# untitled.net
KiCad netlist of a schematic drawn in EAGLE
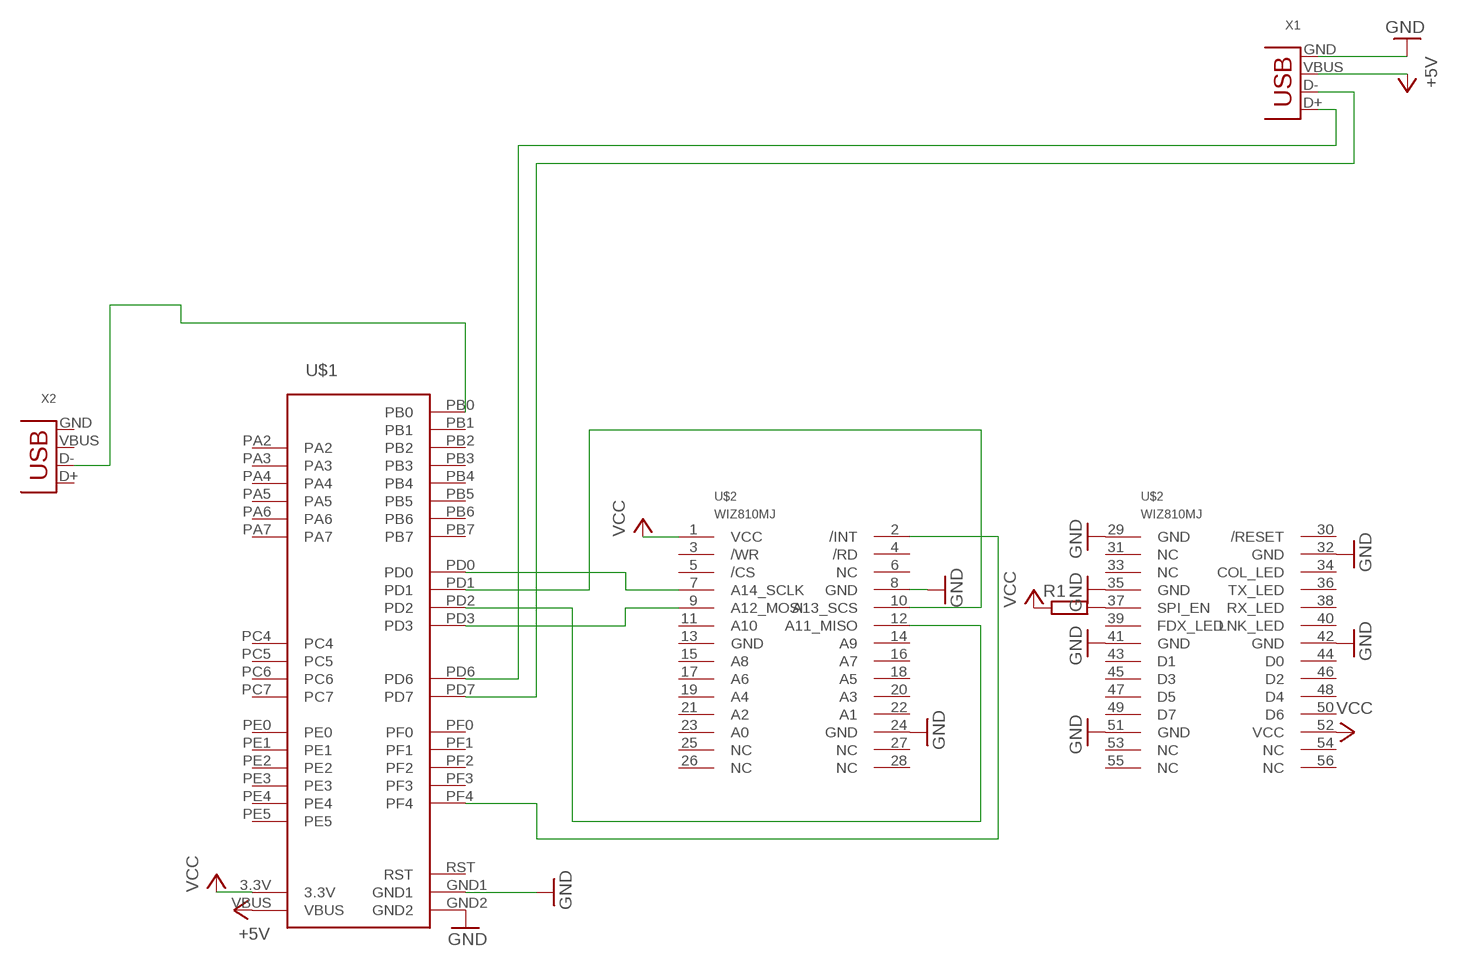
[diagram p0: schematic, sheet 1]

(export (version "E")
  (design (tool "Eeschema 10.0.6"))
  (components
    (comp (ref "R1")
      (value "R-EU_0204/5")
      (footprint "eagle-import:0204_5")
      (libsource (lib "eagle-import") (part "R-EU_0204/5"))
    )
    (comp (ref "U$1")
      (value "STELLARIS-LAUNCHPADSTELLARIS-LAUNCHPAD-XL")
      (footprint "eagle-import:LAUNCHPAD-XL")
      (libsource (lib "eagle-import") (part "STELLARIS-LAUNCHPADSTELLARIS-LAUNCHPAD-XL"))
    )
    (comp (ref "U$2")
      (value "WIZ810MJ")
      (footprint "eagle-import:WIZ810MJ")
      (libsource (lib "eagle-import") (part "WIZ810MJ"))
    )
    (comp (ref "X1")
      (value "USB-A-H")
      (footprint "eagle-import:USB-A-H")
      (libsource (lib "eagle-import") (part "USB-A-H"))
    )
    (comp (ref "X2")
      (value "USB-A-H")
      (footprint "eagle-import:USB-A-H")
      (libsource (lib "eagle-import") (part "USB-A-H"))
    )
  )
  (nets
    (net (code "1") (name "+5V") (class "Default")
      (node (ref "U$1") (pin "VBUS") (pinfunction "VBUS_VBUS") (pintype "power_in"))
      (node (ref "X1") (pin "VBUS") (pinfunction "VBUS_VBUS") (pintype "bidirectional"))
    )
    (net (code "2") (name "/RST") (class "Default")
      (node (ref "U$1") (pin "RST") (pinfunction "RST_RST") (pintype "power_in"))
    )
    (net (code "3") (name "GND") (class "Default")
      (node (ref "U$1") (pin "GND1") (pinfunction "GND1_GND1") (pintype "bidirectional"))
      (node (ref "U$1") (pin "GND2") (pinfunction "GND2_GND2") (pintype "power_in"))
      (node (ref "U$2") (pin "24") (pinfunction "GND_24") (pintype "bidirectional"))
      (node (ref "U$2") (pin "29") (pinfunction "GND_29") (pintype "bidirectional"))
      (node (ref "U$2") (pin "32") (pinfunction "GND_32") (pintype "bidirectional"))
      (node (ref "U$2") (pin "35") (pinfunction "GND_35") (pintype "bidirectional"))
      (node (ref "U$2") (pin "41") (pinfunction "GND_41") (pintype "bidirectional"))
      (node (ref "U$2") (pin "42") (pinfunction "GND_42") (pintype "bidirectional"))
      (node (ref "U$2") (pin "51") (pinfunction "GND_51") (pintype "bidirectional"))
      (node (ref "U$2") (pin "8") (pinfunction "GND_8") (pintype "bidirectional"))
      (node (ref "X1") (pin "GND") (pinfunction "GND_GND") (pintype "bidirectional"))
    )
    (net (code "4") (name "Net-(U$1-PadPB0)") (class "Default")
      (node (ref "U$1") (pin "PB0") (pinfunction "PB0_PB0") (pintype "bidirectional"))
      (node (ref "X2") (pin "D-") (pinfunction "D-_D-") (pintype "bidirectional"))
    )
    (net (code "5") (name "Net-(U$1-PadPD6)") (class "Default")
      (node (ref "U$1") (pin "PD6") (pinfunction "PD6_PD6") (pintype "bidirectional"))
      (node (ref "X1") (pin "D+") (pinfunction "D+_D+") (pintype "bidirectional"))
    )
    (net (code "6") (name "Net-(U$1-PadPD7)") (class "Default")
      (node (ref "U$1") (pin "PD7") (pinfunction "PD7_PD7") (pintype "bidirectional"))
      (node (ref "X1") (pin "D-") (pinfunction "D-_D-") (pintype "bidirectional"))
    )
    (net (code "7") (name "Net-(U$2-A11_MISO)") (class "Default")
      (node (ref "U$1") (pin "PD2") (pinfunction "PD2_PD2") (pintype "bidirectional"))
      (node (ref "U$2") (pin "12") (pinfunction "A11_MISO_12") (pintype "bidirectional"))
    )
    (net (code "8") (name "Net-(U$2-A12_MOSI)") (class "Default")
      (node (ref "U$1") (pin "PD3") (pinfunction "PD3_PD3") (pintype "bidirectional"))
      (node (ref "U$2") (pin "9") (pinfunction "A12_MOSI_9") (pintype "bidirectional"))
    )
    (net (code "9") (name "Net-(U$2-A13_SCS)") (class "Default")
      (node (ref "U$1") (pin "PD1") (pinfunction "PD1_PD1") (pintype "bidirectional"))
      (node (ref "U$2") (pin "10") (pinfunction "A13_SCS_10") (pintype "bidirectional"))
    )
    (net (code "10") (name "Net-(U$2-A14_SCLK)") (class "Default")
      (node (ref "U$1") (pin "PD0") (pinfunction "PD0_PD0") (pintype "bidirectional"))
      (node (ref "U$2") (pin "7") (pinfunction "A14_SCLK_7") (pintype "bidirectional"))
    )
    (net (code "11") (name "Net-(U$2-SPI_EN)") (class "Default")
      (node (ref "R1") (pin "2") (pinfunction "2_2") (pintype "passive"))
      (node (ref "U$2") (pin "37") (pinfunction "SPI_EN_37") (pintype "bidirectional"))
    )
    (net (code "12") (name "Net-(U$2-{slash}INT)") (class "Default")
      (node (ref "U$1") (pin "PF4") (pinfunction "PF4_PF4") (pintype "bidirectional"))
      (node (ref "U$2") (pin "2") (pinfunction "/INT_2") (pintype "bidirectional"))
    )
    (net (code "13") (name "VCC") (class "Default")
      (node (ref "R1") (pin "1") (pinfunction "1_1") (pintype "passive"))
      (node (ref "U$1") (pin "3.3V") (pinfunction "3.3V_3.3V") (pintype "power_in"))
      (node (ref "U$2") (pin "1") (pinfunction "VCC_1") (pintype "bidirectional"))
      (node (ref "U$2") (pin "52") (pinfunction "VCC_52") (pintype "bidirectional"))
    )
    (net (code "14") (name "unconnected-(U$1-PadPA2)") (class "Default")
      (node (ref "U$1") (pin "PA2") (pinfunction "PA2_PA2") (pintype "bidirectional"))
    )
    (net (code "15") (name "unconnected-(U$1-PadPA3)") (class "Default")
      (node (ref "U$1") (pin "PA3") (pinfunction "PA3_PA3") (pintype "bidirectional"))
    )
    (net (code "16") (name "unconnected-(U$1-PadPA4)") (class "Default")
      (node (ref "U$1") (pin "PA4") (pinfunction "PA4_PA4") (pintype "bidirectional"))
    )
    (net (code "17") (name "unconnected-(U$1-PadPA5)") (class "Default")
      (node (ref "U$1") (pin "PA5") (pinfunction "PA5_PA5") (pintype "bidirectional"))
    )
    (net (code "18") (name "unconnected-(U$1-PadPA6)") (class "Default")
      (node (ref "U$1") (pin "PA6") (pinfunction "PA6_PA6") (pintype "bidirectional"))
    )
    (net (code "19") (name "unconnected-(U$1-PadPA7)") (class "Default")
      (node (ref "U$1") (pin "PA7") (pinfunction "PA7_PA7") (pintype "bidirectional"))
    )
    (net (code "20") (name "unconnected-(U$1-PadPB1)") (class "Default")
      (node (ref "U$1") (pin "PB1") (pinfunction "PB1_PB1") (pintype "bidirectional"))
    )
    (net (code "21") (name "unconnected-(U$1-PadPB2)") (class "Default")
      (node (ref "U$1") (pin "PB2") (pinfunction "PB2_PB2") (pintype "bidirectional"))
    )
    (net (code "22") (name "unconnected-(U$1-PadPB3)") (class "Default")
      (node (ref "U$1") (pin "PB3") (pinfunction "PB3_PB3") (pintype "bidirectional"))
    )
    (net (code "23") (name "unconnected-(U$1-PadPB4)") (class "Default")
      (node (ref "U$1") (pin "PB4") (pinfunction "PB4_PB4") (pintype "bidirectional"))
    )
    (net (code "24") (name "unconnected-(U$1-PadPB5)") (class "Default")
      (node (ref "U$1") (pin "PB5") (pinfunction "PB5_PB5") (pintype "bidirectional"))
    )
    (net (code "25") (name "unconnected-(U$1-PadPB6)") (class "Default")
      (node (ref "U$1") (pin "PB6") (pinfunction "PB6_PB6") (pintype "bidirectional"))
    )
    (net (code "26") (name "unconnected-(U$1-PadPB7)") (class "Default")
      (node (ref "U$1") (pin "PB7") (pinfunction "PB7_PB7") (pintype "bidirectional"))
    )
    (net (code "27") (name "unconnected-(U$1-PadPC4)") (class "Default")
      (node (ref "U$1") (pin "PC4") (pinfunction "PC4_PC4") (pintype "bidirectional"))
    )
    (net (code "28") (name "unconnected-(U$1-PadPC5)") (class "Default")
      (node (ref "U$1") (pin "PC5") (pinfunction "PC5_PC5") (pintype "bidirectional"))
    )
    (net (code "29") (name "unconnected-(U$1-PadPC6)") (class "Default")
      (node (ref "U$1") (pin "PC6") (pinfunction "PC6_PC6") (pintype "bidirectional"))
    )
    (net (code "30") (name "unconnected-(U$1-PadPC7)") (class "Default")
      (node (ref "U$1") (pin "PC7") (pinfunction "PC7_PC7") (pintype "bidirectional"))
    )
    (net (code "31") (name "unconnected-(U$1-PadPE0)") (class "Default")
      (node (ref "U$1") (pin "PE0") (pinfunction "PE0_PE0") (pintype "bidirectional"))
    )
    (net (code "32") (name "unconnected-(U$1-PadPE1)") (class "Default")
      (node (ref "U$1") (pin "PE1") (pinfunction "PE1_PE1") (pintype "bidirectional"))
    )
    (net (code "33") (name "unconnected-(U$1-PadPE2)") (class "Default")
      (node (ref "U$1") (pin "PE2") (pinfunction "PE2_PE2") (pintype "bidirectional"))
    )
    (net (code "34") (name "unconnected-(U$1-PadPE3)") (class "Default")
      (node (ref "U$1") (pin "PE3") (pinfunction "PE3_PE3") (pintype "bidirectional"))
    )
    (net (code "35") (name "unconnected-(U$1-PadPE4)") (class "Default")
      (node (ref "U$1") (pin "PE4") (pinfunction "PE4_PE4") (pintype "bidirectional"))
    )
    (net (code "36") (name "unconnected-(U$1-PadPE5)") (class "Default")
      (node (ref "U$1") (pin "PE5") (pinfunction "PE5_PE5") (pintype "bidirectional"))
    )
    (net (code "37") (name "unconnected-(U$1-PadPF0)") (class "Default")
      (node (ref "U$1") (pin "PF0") (pinfunction "PF0_PF0") (pintype "bidirectional"))
    )
    (net (code "38") (name "unconnected-(U$1-PadPF1)") (class "Default")
      (node (ref "U$1") (pin "PF1") (pinfunction "PF1_PF1") (pintype "bidirectional"))
    )
    (net (code "39") (name "unconnected-(U$1-PadPF2)") (class "Default")
      (node (ref "U$1") (pin "PF2") (pinfunction "PF2_PF2") (pintype "bidirectional"))
    )
    (net (code "40") (name "unconnected-(U$1-PadPF3)") (class "Default")
      (node (ref "U$1") (pin "PF3") (pinfunction "PF3_PF3") (pintype "bidirectional"))
    )
    (net (code "41") (name "unconnected-(U$2-A0-Pad23)") (class "Default")
      (node (ref "U$2") (pin "23") (pinfunction "A0_23") (pintype "bidirectional"))
    )
    (net (code "42") (name "unconnected-(U$2-A1-Pad22)") (class "Default")
      (node (ref "U$2") (pin "22") (pinfunction "A1_22") (pintype "bidirectional"))
    )
    (net (code "43") (name "unconnected-(U$2-A2-Pad21)") (class "Default")
      (node (ref "U$2") (pin "21") (pinfunction "A2_21") (pintype "bidirectional"))
    )
    (net (code "44") (name "unconnected-(U$2-A3-Pad20)") (class "Default")
      (node (ref "U$2") (pin "20") (pinfunction "A3_20") (pintype "bidirectional"))
    )
    (net (code "45") (name "unconnected-(U$2-A4-Pad19)") (class "Default")
      (node (ref "U$2") (pin "19") (pinfunction "A4_19") (pintype "bidirectional"))
    )
    (net (code "46") (name "unconnected-(U$2-A5-Pad18)") (class "Default")
      (node (ref "U$2") (pin "18") (pinfunction "A5_18") (pintype "bidirectional"))
    )
    (net (code "47") (name "unconnected-(U$2-A6-Pad17)") (class "Default")
      (node (ref "U$2") (pin "17") (pinfunction "A6_17") (pintype "bidirectional"))
    )
    (net (code "48") (name "unconnected-(U$2-A7-Pad16)") (class "Default")
      (node (ref "U$2") (pin "16") (pinfunction "A7_16") (pintype "bidirectional"))
    )
    (net (code "49") (name "unconnected-(U$2-A8-Pad15)") (class "Default")
      (node (ref "U$2") (pin "15") (pinfunction "A8_15") (pintype "bidirectional"))
    )
    (net (code "50") (name "unconnected-(U$2-A9-Pad14)") (class "Default")
      (node (ref "U$2") (pin "14") (pinfunction "A9_14") (pintype "bidirectional"))
    )
    (net (code "51") (name "unconnected-(U$2-A10-Pad11)") (class "Default")
      (node (ref "U$2") (pin "11") (pinfunction "A10_11") (pintype "bidirectional"))
    )
    (net (code "52") (name "unconnected-(U$2-COL_LED-Pad34)") (class "Default")
      (node (ref "U$2") (pin "34") (pinfunction "COL_LED_34") (pintype "bidirectional"))
    )
    (net (code "53") (name "unconnected-(U$2-D0-Pad44)") (class "Default")
      (node (ref "U$2") (pin "44") (pinfunction "D0_44") (pintype "bidirectional"))
    )
    (net (code "54") (name "unconnected-(U$2-D1-Pad43)") (class "Default")
      (node (ref "U$2") (pin "43") (pinfunction "D1_43") (pintype "bidirectional"))
    )
    (net (code "55") (name "unconnected-(U$2-D2-Pad46)") (class "Default")
      (node (ref "U$2") (pin "46") (pinfunction "D2_46") (pintype "bidirectional"))
    )
    (net (code "56") (name "unconnected-(U$2-D3-Pad45)") (class "Default")
      (node (ref "U$2") (pin "45") (pinfunction "D3_45") (pintype "bidirectional"))
    )
    (net (code "57") (name "unconnected-(U$2-D4-Pad48)") (class "Default")
      (node (ref "U$2") (pin "48") (pinfunction "D4_48") (pintype "bidirectional"))
    )
    (net (code "58") (name "unconnected-(U$2-D5-Pad47)") (class "Default")
      (node (ref "U$2") (pin "47") (pinfunction "D5_47") (pintype "bidirectional"))
    )
    (net (code "59") (name "unconnected-(U$2-D6-Pad50)") (class "Default")
      (node (ref "U$2") (pin "50") (pinfunction "D6_50") (pintype "bidirectional"))
    )
    (net (code "60") (name "unconnected-(U$2-D7-Pad49)") (class "Default")
      (node (ref "U$2") (pin "49") (pinfunction "D7_49") (pintype "bidirectional"))
    )
    (net (code "61") (name "unconnected-(U$2-FDX_LED-Pad39)") (class "Default")
      (node (ref "U$2") (pin "39") (pinfunction "FDX_LED_39") (pintype "bidirectional"))
    )
    (net (code "62") (name "unconnected-(U$2-GND-Pad13)") (class "Default")
      (node (ref "U$2") (pin "13") (pinfunction "GND_13") (pintype "bidirectional"))
    )
    (net (code "63") (name "unconnected-(U$2-LNK_LED-Pad40)") (class "Default")
      (node (ref "U$2") (pin "40") (pinfunction "LNK_LED_40") (pintype "bidirectional"))
    )
    (net (code "64") (name "unconnected-(U$2-NC-Pad6)") (class "Default")
      (node (ref "U$2") (pin "6") (pinfunction "NC_6") (pintype "bidirectional"))
    )
    (net (code "65") (name "unconnected-(U$2-NC-Pad25)") (class "Default")
      (node (ref "U$2") (pin "25") (pinfunction "NC_25") (pintype "bidirectional"))
    )
    (net (code "66") (name "unconnected-(U$2-NC-Pad26)") (class "Default")
      (node (ref "U$2") (pin "26") (pinfunction "NC_26") (pintype "bidirectional"))
    )
    (net (code "67") (name "unconnected-(U$2-NC-Pad27)") (class "Default")
      (node (ref "U$2") (pin "27") (pinfunction "NC_27") (pintype "bidirectional"))
    )
    (net (code "68") (name "unconnected-(U$2-NC-Pad28)") (class "Default")
      (node (ref "U$2") (pin "28") (pinfunction "NC_28") (pintype "bidirectional"))
    )
    (net (code "69") (name "unconnected-(U$2-NC-Pad31)") (class "Default")
      (node (ref "U$2") (pin "31") (pinfunction "NC_31") (pintype "bidirectional"))
    )
    (net (code "70") (name "unconnected-(U$2-NC-Pad33)") (class "Default")
      (node (ref "U$2") (pin "33") (pinfunction "NC_33") (pintype "bidirectional"))
    )
    (net (code "71") (name "unconnected-(U$2-NC-Pad53)") (class "Default")
      (node (ref "U$2") (pin "53") (pinfunction "NC_53") (pintype "bidirectional"))
    )
    (net (code "72") (name "unconnected-(U$2-NC-Pad54)") (class "Default")
      (node (ref "U$2") (pin "54") (pinfunction "NC_54") (pintype "bidirectional"))
    )
    (net (code "73") (name "unconnected-(U$2-NC-Pad55)") (class "Default")
      (node (ref "U$2") (pin "55") (pinfunction "NC_55") (pintype "bidirectional"))
    )
    (net (code "74") (name "unconnected-(U$2-NC-Pad56)") (class "Default")
      (node (ref "U$2") (pin "56") (pinfunction "NC_56") (pintype "bidirectional"))
    )
    (net (code "75") (name "unconnected-(U$2-RX_LED-Pad38)") (class "Default")
      (node (ref "U$2") (pin "38") (pinfunction "RX_LED_38") (pintype "bidirectional"))
    )
    (net (code "76") (name "unconnected-(U$2-TX_LED-Pad36)") (class "Default")
      (node (ref "U$2") (pin "36") (pinfunction "TX_LED_36") (pintype "bidirectional"))
    )
    (net (code "77") (name "unconnected-(U$2-{slash}CS-Pad5)") (class "Default")
      (node (ref "U$2") (pin "5") (pinfunction "/CS_5") (pintype "bidirectional"))
    )
    (net (code "78") (name "unconnected-(U$2-{slash}RD-Pad4)") (class "Default")
      (node (ref "U$2") (pin "4") (pinfunction "/RD_4") (pintype "bidirectional"))
    )
    (net (code "79") (name "unconnected-(U$2-{slash}RESET-Pad30)") (class "Default")
      (node (ref "U$2") (pin "30") (pinfunction "/RESET_30") (pintype "bidirectional"))
    )
    (net (code "80") (name "unconnected-(U$2-{slash}WR-Pad3)") (class "Default")
      (node (ref "U$2") (pin "3") (pinfunction "/WR_3") (pintype "bidirectional"))
    )
    (net (code "81") (name "unconnected-(X2-PadD+)") (class "Default")
      (node (ref "X2") (pin "D+") (pinfunction "D+_D+") (pintype "bidirectional"))
    )
    (net (code "82") (name "unconnected-(X2-PadGND)") (class "Default")
      (node (ref "X2") (pin "GND") (pinfunction "GND_GND") (pintype "bidirectional"))
    )
    (net (code "83") (name "unconnected-(X2-PadVBUS)") (class "Default")
      (node (ref "X2") (pin "VBUS") (pinfunction "VBUS_VBUS") (pintype "bidirectional"))
    )
  )
)
